# sensors.net
KiCad netlist of a schematic drawn in EAGLE
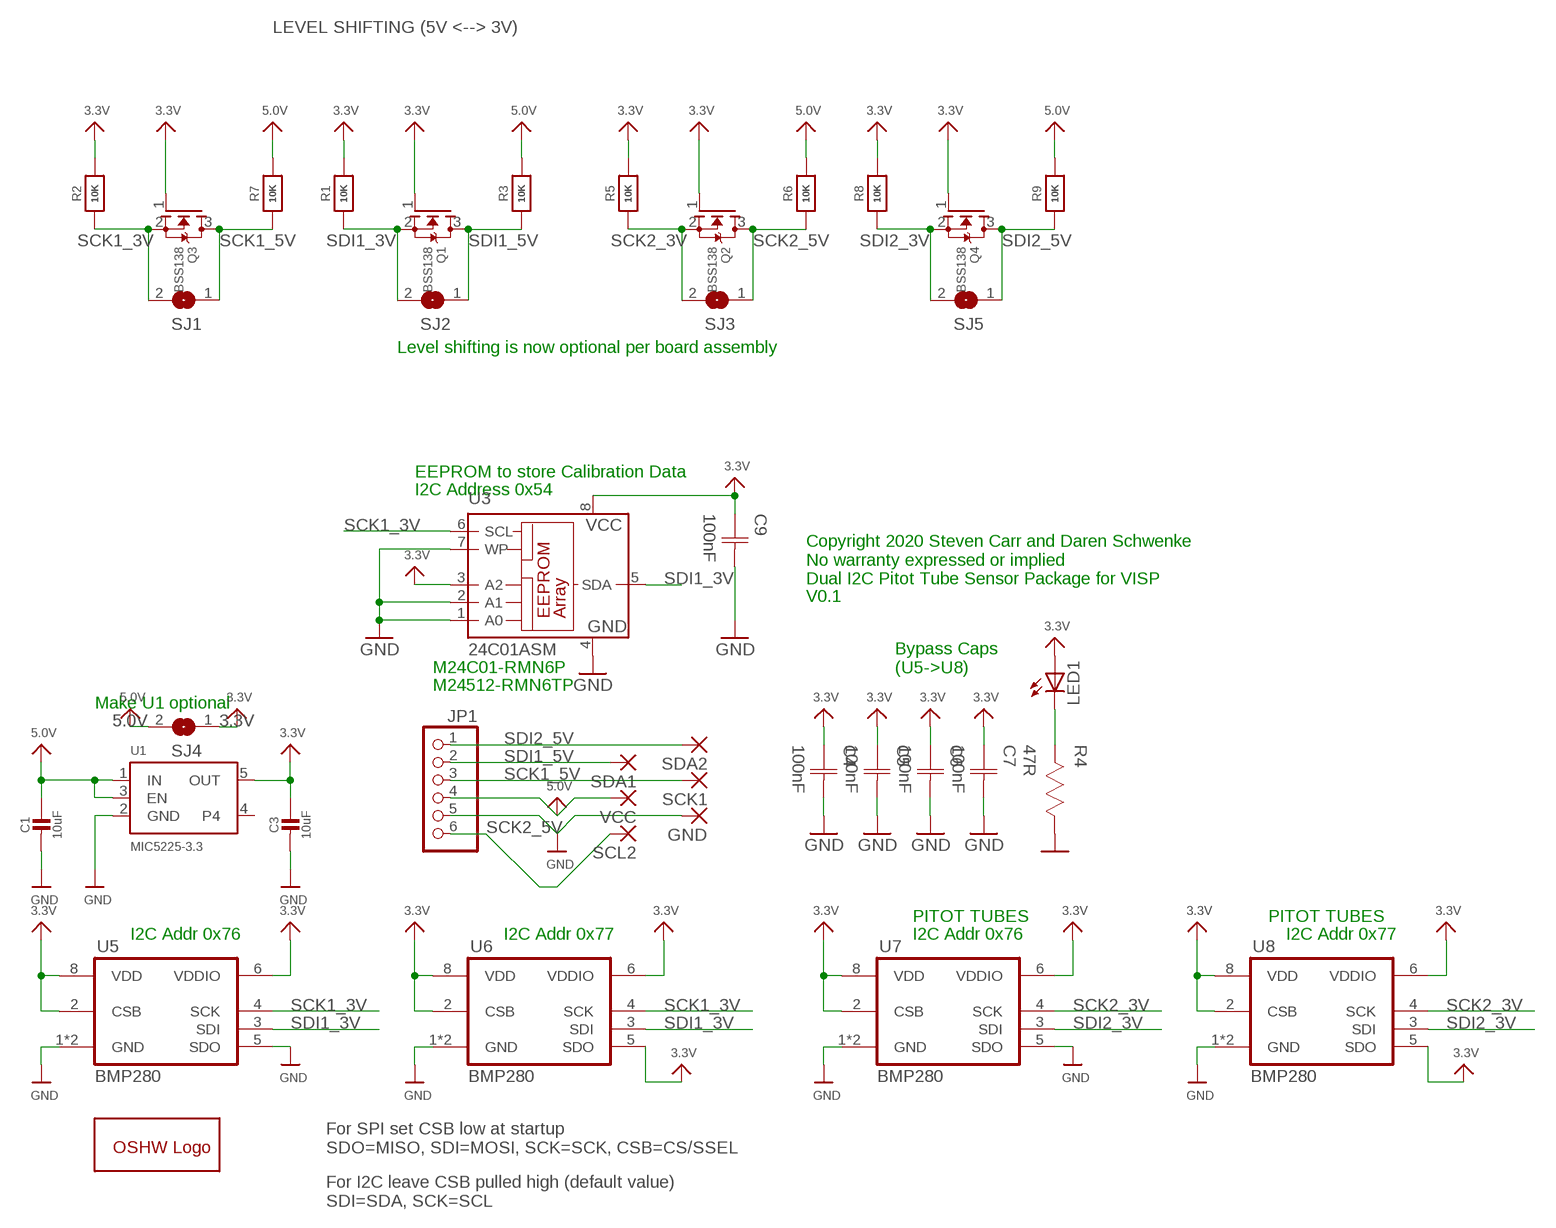
[diagram p0: schematic, sheet 1]

(export (version "E")
  (design (tool "Eeschema 10.0.6"))
  (components
    (comp (ref "C1")
      (value "10uF")
      (footprint "eagle-import:_0805")
      (fields (field (name "MPN") "C1608X5R1A106M080AC"))
      (libsource (lib "eagle-import") (part "CAP_CERAMIC_0805"))
    )
    (comp (ref "C3")
      (value "10uF")
      (footprint "eagle-import:_0805")
      (fields (field (name "MPN") "C1608X5R1A106M080AC"))
      (libsource (lib "eagle-import") (part "CAP_CERAMIC_0805"))
    )
    (comp (ref "C4")
      (value "100nF")
      (footprint "eagle-import:CAP0402")
      (fields (field (name "MPN") " CL10F104ZO8NNNC "))
      (libsource (lib "eagle-import") (part "CAPACITOR-0402"))
    )
    (comp (ref "C5")
      (value "100nF")
      (footprint "eagle-import:CAP0402")
      (fields (field (name "MPN") " CL10F104ZO8NNNC "))
      (libsource (lib "eagle-import") (part "CAPACITOR-0402"))
    )
    (comp (ref "C6")
      (value "100nF")
      (footprint "eagle-import:CAP0402")
      (fields (field (name "MPN") " CL10F104ZO8NNNC "))
      (libsource (lib "eagle-import") (part "CAPACITOR-0402"))
    )
    (comp (ref "C7")
      (value "100nF")
      (footprint "eagle-import:CAP0402")
      (fields (field (name "MPN") " CL10F104ZO8NNNC "))
      (libsource (lib "eagle-import") (part "CAPACITOR-0402"))
    )
    (comp (ref "C9")
      (value "100nF")
      (footprint "eagle-import:CAP0402")
      (fields (field (name "MPN") "CL10B104KB8NNNC"))
      (libsource (lib "eagle-import") (part "CAPACITOR-0402"))
    )
    (comp (ref "GND")
      (value "SMD2")
      (footprint "eagle-import:SMD1,27-2,54")
      (libsource (lib "eagle-import") (part "SMD2"))
    )
    (comp (ref "GOLD_ORB_SM1")
      (value "OSHWLOGOLOGO8MM")
      (footprint "eagle-import:OSHW_8MM")
      (libsource (lib "eagle-import") (part "OSHWLOGOLOGO8MM"))
    )
    (comp (ref "JP1")
      (value "PINHD-1X6")
      (footprint "eagle-import:1X06")
      (libsource (lib "eagle-import") (part "PINHD-1X6"))
    )
    (comp (ref "LED1")
      (value "LEDCHIP-LED0603")
      (footprint "eagle-import:CHIP-LED0603")
      (fields (field (name "MPN") "SML-D12P8WT86"))
      (libsource (lib "eagle-import") (part "LEDCHIP-LED0603"))
    )
    (comp (ref "Q1")
      (value "BSS138")
      (footprint "eagle-import:SOT23-WIDE")
      (libsource (lib "eagle-import") (part "MOSFET-NWIDE"))
    )
    (comp (ref "Q2")
      (value "BSS138")
      (footprint "eagle-import:SOT23-WIDE")
      (libsource (lib "eagle-import") (part "MOSFET-NWIDE"))
    )
    (comp (ref "Q3")
      (value "BSS138")
      (footprint "eagle-import:SOT23-WIDE")
      (libsource (lib "eagle-import") (part "MOSFET-NWIDE"))
    )
    (comp (ref "Q4")
      (value "BSS138")
      (footprint "eagle-import:SOT23-WIDE")
      (libsource (lib "eagle-import") (part "MOSFET-NWIDE"))
    )
    (comp (ref "R1")
      (value "10K")
      (footprint "eagle-import:_0402")
      (libsource (lib "eagle-import") (part "RESISTOR_0402"))
    )
    (comp (ref "R2")
      (value "10K")
      (footprint "eagle-import:_0402")
      (libsource (lib "eagle-import") (part "RESISTOR_0402"))
    )
    (comp (ref "R3")
      (value "10K")
      (footprint "eagle-import:_0402")
      (libsource (lib "eagle-import") (part "RESISTOR_0402"))
    )
    (comp (ref "R4")
      (value "47R")
      (footprint "eagle-import:RES0402")
      (fields (field (name "MPN") "RC0603FR-0747RL"))
      (libsource (lib "eagle-import") (part "RESISTOR-0402"))
    )
    (comp (ref "R5")
      (value "10K")
      (footprint "eagle-import:_0402")
      (libsource (lib "eagle-import") (part "RESISTOR_0402"))
    )
    (comp (ref "R6")
      (value "10K")
      (footprint "eagle-import:_0402")
      (libsource (lib "eagle-import") (part "RESISTOR_0402"))
    )
    (comp (ref "R7")
      (value "10K")
      (footprint "eagle-import:_0402")
      (libsource (lib "eagle-import") (part "RESISTOR_0402"))
    )
    (comp (ref "R8")
      (value "10K")
      (footprint "eagle-import:_0402")
      (libsource (lib "eagle-import") (part "RESISTOR_0402"))
    )
    (comp (ref "R9")
      (value "10K")
      (footprint "eagle-import:_0402")
      (libsource (lib "eagle-import") (part "RESISTOR_0402"))
    )
    (comp (ref "SCK1")
      (value "SMD2")
      (footprint "eagle-import:SMD1,27-2,54")
      (libsource (lib "eagle-import") (part "SMD2"))
    )
    (comp (ref "SCL2")
      (value "SMD2")
      (footprint "eagle-import:SMD1,27-2,54")
      (libsource (lib "eagle-import") (part "SMD2"))
    )
    (comp (ref "SDA1")
      (value "SMD2")
      (footprint "eagle-import:SMD1,27-2,54")
      (libsource (lib "eagle-import") (part "SMD2"))
    )
    (comp (ref "SDA2")
      (value "SMD2")
      (footprint "eagle-import:SMD1,27-2,54")
      (libsource (lib "eagle-import") (part "SMD2"))
    )
    (comp (ref "SJ1") (value "SJ") (footprint "eagle-import:SJ") (libsource (lib "eagle-import") (part "SJ")))
    (comp (ref "SJ2") (value "SJ") (footprint "eagle-import:SJ") (libsource (lib "eagle-import") (part "SJ")))
    (comp (ref "SJ3") (value "SJ") (footprint "eagle-import:SJ") (libsource (lib "eagle-import") (part "SJ")))
    (comp (ref "SJ4") (value "SJ") (footprint "eagle-import:SJ") (libsource (lib "eagle-import") (part "SJ")))
    (comp (ref "SJ5") (value "SJ") (footprint "eagle-import:SJ") (libsource (lib "eagle-import") (part "SJ")))
    (comp (ref "U1")
      (value "MIC5225-3.3")
      (footprint "eagle-import:SOT23-5")
      (fields (field (name "MPN") "MIC5225-3.3YM5-TR"))
      (libsource (lib "eagle-import") (part "VREG_SOT23-5"))
    )
    (comp (ref "U3")
      (value "24C01ASM")
      (footprint "eagle-import:SO-08M")
      (fields
        (field (name "MF") "MICROCHIP")
        (field (name "MPN") "24C01C/SN")
        (field (name "MPN_1") "M24C01-RMN6P")
      )
      (libsource (lib "eagle-import") (part "24SMC01A"))
    )
    (comp (ref "U5")
      (value "BMP280")
      (footprint "eagle-import:BMP280")
      (libsource (lib "eagle-import") (part "BMP280"))
    )
    (comp (ref "U6")
      (value "BMP280")
      (footprint "eagle-import:BMP280")
      (libsource (lib "eagle-import") (part "BMP280"))
    )
    (comp (ref "U7")
      (value "BMP280")
      (footprint "eagle-import:BMP280")
      (libsource (lib "eagle-import") (part "BMP280"))
    )
    (comp (ref "U8")
      (value "BMP280")
      (footprint "eagle-import:BMP280")
      (libsource (lib "eagle-import") (part "BMP280"))
    )
    (comp (ref "VCC")
      (value "SMD2")
      (footprint "eagle-import:SMD1,27-2,54")
      (libsource (lib "eagle-import") (part "SMD2"))
    )
  )
  (nets
    (net (code "1") (name "/SCK1_3V") (class "Default")
      (node (ref "Q3") (pin "2") (pinfunction "S_2") (pintype "bidirectional"))
      (node (ref "R2") (pin "1") (pinfunction "1_1") (pintype "passive"))
      (node (ref "SJ1") (pin "2") (pinfunction "2_2") (pintype "passive"))
      (node (ref "U3") (pin "6") (pinfunction "SCL_6") (pintype "input"))
      (node (ref "U5") (pin "4") (pinfunction "SCK_4") (pintype "bidirectional"))
      (node (ref "U6") (pin "4") (pinfunction "SCK_4") (pintype "bidirectional"))
    )
    (net (code "2") (name "/SCK1_5V") (class "Default")
      (node (ref "JP1") (pin "3") (pinfunction "3_3") (pintype "passive"))
      (node (ref "Q3") (pin "3") (pinfunction "D_3") (pintype "bidirectional"))
      (node (ref "R7") (pin "1") (pinfunction "1_1") (pintype "passive"))
      (node (ref "SCK1") (pin "1") (pinfunction "P_1") (pintype "passive"))
      (node (ref "SJ1") (pin "1") (pinfunction "1_1") (pintype "passive"))
    )
    (net (code "3") (name "/SCK2_3V") (class "Default")
      (node (ref "Q2") (pin "2") (pinfunction "S_2") (pintype "bidirectional"))
      (node (ref "R5") (pin "1") (pinfunction "1_1") (pintype "passive"))
      (node (ref "SJ3") (pin "2") (pinfunction "2_2") (pintype "passive"))
      (node (ref "U7") (pin "4") (pinfunction "SCK_4") (pintype "bidirectional"))
      (node (ref "U8") (pin "4") (pinfunction "SCK_4") (pintype "bidirectional"))
    )
    (net (code "4") (name "/SCK2_5V") (class "Default")
      (node (ref "JP1") (pin "6") (pinfunction "6_6") (pintype "passive"))
      (node (ref "Q2") (pin "3") (pinfunction "D_3") (pintype "bidirectional"))
      (node (ref "R6") (pin "1") (pinfunction "1_1") (pintype "passive"))
      (node (ref "SCL2") (pin "1") (pinfunction "P_1") (pintype "passive"))
      (node (ref "SJ3") (pin "1") (pinfunction "1_1") (pintype "passive"))
    )
    (net (code "5") (name "/SDI1_3V") (class "Default")
      (node (ref "Q1") (pin "2") (pinfunction "S_2") (pintype "bidirectional"))
      (node (ref "R1") (pin "1") (pinfunction "1_1") (pintype "passive"))
      (node (ref "SJ2") (pin "2") (pinfunction "2_2") (pintype "passive"))
      (node (ref "U3") (pin "5") (pinfunction "SDA_5") (pintype "bidirectional"))
      (node (ref "U5") (pin "3") (pinfunction "SDI_3") (pintype "bidirectional"))
      (node (ref "U6") (pin "3") (pinfunction "SDI_3") (pintype "bidirectional"))
    )
    (net (code "6") (name "/SDI1_5V") (class "Default")
      (node (ref "JP1") (pin "2") (pinfunction "2_2") (pintype "passive"))
      (node (ref "Q1") (pin "3") (pinfunction "D_3") (pintype "bidirectional"))
      (node (ref "R3") (pin "1") (pinfunction "1_1") (pintype "passive"))
      (node (ref "SDA1") (pin "1") (pinfunction "P_1") (pintype "passive"))
      (node (ref "SJ2") (pin "1") (pinfunction "1_1") (pintype "passive"))
    )
    (net (code "7") (name "/SDI2_3V") (class "Default")
      (node (ref "Q4") (pin "2") (pinfunction "S_2") (pintype "bidirectional"))
      (node (ref "R8") (pin "1") (pinfunction "1_1") (pintype "passive"))
      (node (ref "SJ5") (pin "2") (pinfunction "2_2") (pintype "passive"))
      (node (ref "U7") (pin "3") (pinfunction "SDI_3") (pintype "bidirectional"))
      (node (ref "U8") (pin "3") (pinfunction "SDI_3") (pintype "bidirectional"))
    )
    (net (code "8") (name "/SDI2_5V") (class "Default")
      (node (ref "JP1") (pin "1") (pinfunction "1_1") (pintype "passive"))
      (node (ref "Q4") (pin "3") (pinfunction "D_3") (pintype "bidirectional"))
      (node (ref "R9") (pin "1") (pinfunction "1_1") (pintype "passive"))
      (node (ref "SDA2") (pin "1") (pinfunction "P_1") (pintype "passive"))
      (node (ref "SJ5") (pin "1") (pinfunction "1_1") (pintype "passive"))
    )
    (net (code "9") (name "3.3V") (class "Default")
      (node (ref "C3") (pin "1") (pinfunction "1_1") (pintype "passive"))
      (node (ref "C4") (pin "1") (pinfunction "C1_1") (pintype "passive"))
      (node (ref "C5") (pin "1") (pinfunction "C1_1") (pintype "passive"))
      (node (ref "C6") (pin "1") (pinfunction "C1_1") (pintype "passive"))
      (node (ref "C7") (pin "1") (pinfunction "C1_1") (pintype "passive"))
      (node (ref "C9") (pin "1") (pinfunction "C1_1") (pintype "passive"))
      (node (ref "LED1") (pin "A") (pinfunction "A_A") (pintype "passive"))
      (node (ref "Q1") (pin "1") (pinfunction "G_1") (pintype "bidirectional"))
      (node (ref "Q2") (pin "1") (pinfunction "G_1") (pintype "bidirectional"))
      (node (ref "Q3") (pin "1") (pinfunction "G_1") (pintype "bidirectional"))
      (node (ref "Q4") (pin "1") (pinfunction "G_1") (pintype "bidirectional"))
      (node (ref "R1") (pin "2") (pinfunction "2_2") (pintype "passive"))
      (node (ref "R2") (pin "2") (pinfunction "2_2") (pintype "passive"))
      (node (ref "R5") (pin "2") (pinfunction "2_2") (pintype "passive"))
      (node (ref "R8") (pin "2") (pinfunction "2_2") (pintype "passive"))
      (node (ref "SJ4") (pin "1") (pinfunction "1_1") (pintype "passive"))
      (node (ref "U1") (pin "5") (pinfunction "OUT_5") (pintype "power_in"))
      (node (ref "U3") (pin "3") (pinfunction "A2_3") (pintype "input"))
      (node (ref "U3") (pin "8") (pinfunction "VCC_8") (pintype "power_in"))
      (node (ref "U5") (pin "2") (pinfunction "CSB_2") (pintype "input"))
      (node (ref "U5") (pin "6") (pinfunction "VDDIO_6") (pintype "power_in"))
      (node (ref "U5") (pin "8") (pinfunction "VDD_8") (pintype "power_in"))
      (node (ref "U6") (pin "2") (pinfunction "CSB_2") (pintype "input"))
      (node (ref "U6") (pin "5") (pinfunction "SDO_5") (pintype "input"))
      (node (ref "U6") (pin "6") (pinfunction "VDDIO_6") (pintype "power_in"))
      (node (ref "U6") (pin "8") (pinfunction "VDD_8") (pintype "power_in"))
      (node (ref "U7") (pin "2") (pinfunction "CSB_2") (pintype "input"))
      (node (ref "U7") (pin "6") (pinfunction "VDDIO_6") (pintype "power_in"))
      (node (ref "U7") (pin "8") (pinfunction "VDD_8") (pintype "power_in"))
      (node (ref "U8") (pin "2") (pinfunction "CSB_2") (pintype "input"))
      (node (ref "U8") (pin "5") (pinfunction "SDO_5") (pintype "input"))
      (node (ref "U8") (pin "6") (pinfunction "VDDIO_6") (pintype "power_in"))
      (node (ref "U8") (pin "8") (pinfunction "VDD_8") (pintype "power_in"))
    )
    (net (code "10") (name "5.0V") (class "Default")
      (node (ref "C1") (pin "1") (pinfunction "1_1") (pintype "passive"))
      (node (ref "JP1") (pin "4") (pinfunction "4_4") (pintype "passive"))
      (node (ref "R3") (pin "2") (pinfunction "2_2") (pintype "passive"))
      (node (ref "R6") (pin "2") (pinfunction "2_2") (pintype "passive"))
      (node (ref "R7") (pin "2") (pinfunction "2_2") (pintype "passive"))
      (node (ref "R9") (pin "2") (pinfunction "2_2") (pintype "passive"))
      (node (ref "SJ4") (pin "2") (pinfunction "2_2") (pintype "passive"))
      (node (ref "U1") (pin "1") (pinfunction "IN_1") (pintype "power_in"))
      (node (ref "U1") (pin "3") (pinfunction "EN_3") (pintype "input"))
      (node (ref "VCC") (pin "1") (pinfunction "P_1") (pintype "passive"))
    )
    (net (code "11") (name "GND") (class "Default")
      (node (ref "C1") (pin "2") (pinfunction "2_2") (pintype "passive"))
      (node (ref "C3") (pin "2") (pinfunction "2_2") (pintype "passive"))
      (node (ref "C4") (pin "2") (pinfunction "C2_2") (pintype "passive"))
      (node (ref "C5") (pin "2") (pinfunction "C2_2") (pintype "passive"))
      (node (ref "C6") (pin "2") (pinfunction "C2_2") (pintype "passive"))
      (node (ref "C7") (pin "2") (pinfunction "C2_2") (pintype "passive"))
      (node (ref "C9") (pin "2") (pinfunction "C2_2") (pintype "passive"))
      (node (ref "GND") (pin "1") (pinfunction "P_1") (pintype "passive"))
      (node (ref "JP1") (pin "5") (pinfunction "5_5") (pintype "passive"))
      (node (ref "R4") (pin "1") (pinfunction "1_1") (pintype "passive"))
      (node (ref "U1") (pin "2") (pinfunction "GND_2") (pintype "power_in"))
      (node (ref "U3") (pin "1") (pinfunction "A0_1") (pintype "input"))
      (node (ref "U3") (pin "2") (pinfunction "A1_2") (pintype "input"))
      (node (ref "U3") (pin "4") (pinfunction "GND_4") (pintype "power_in"))
      (node (ref "U3") (pin "7") (pinfunction "WP_7") (pintype "input"))
      (node (ref "U5") (pin "1") (pinfunction "GND_1") (pintype "power_in"))
      (node (ref "U5") (pin "5") (pinfunction "SDO_5") (pintype "input"))
      (node (ref "U5") (pin "7") (pinfunction "GND_7") (pintype "power_in"))
      (node (ref "U6") (pin "1") (pinfunction "GND_1") (pintype "power_in"))
      (node (ref "U6") (pin "7") (pinfunction "GND_7") (pintype "power_in"))
      (node (ref "U7") (pin "1") (pinfunction "GND_1") (pintype "power_in"))
      (node (ref "U7") (pin "5") (pinfunction "SDO_5") (pintype "input"))
      (node (ref "U7") (pin "7") (pinfunction "GND_7") (pintype "power_in"))
      (node (ref "U8") (pin "1") (pinfunction "GND_1") (pintype "power_in"))
      (node (ref "U8") (pin "7") (pinfunction "GND_7") (pintype "power_in"))
    )
    (net (code "12") (name "Net-(LED1-PadC)") (class "Default")
      (node (ref "LED1") (pin "C") (pinfunction "C_C") (pintype "passive"))
      (node (ref "R4") (pin "2") (pinfunction "2_2") (pintype "passive"))
    )
    (net (code "13") (name "unconnected-(U1-P4-Pad4)") (class "Default")
      (node (ref "U1") (pin "4") (pinfunction "P4_4") (pintype "bidirectional"))
    )
  )
)
